# 2021.net
KiCad netlist of a schematic drawn in Altium Designer
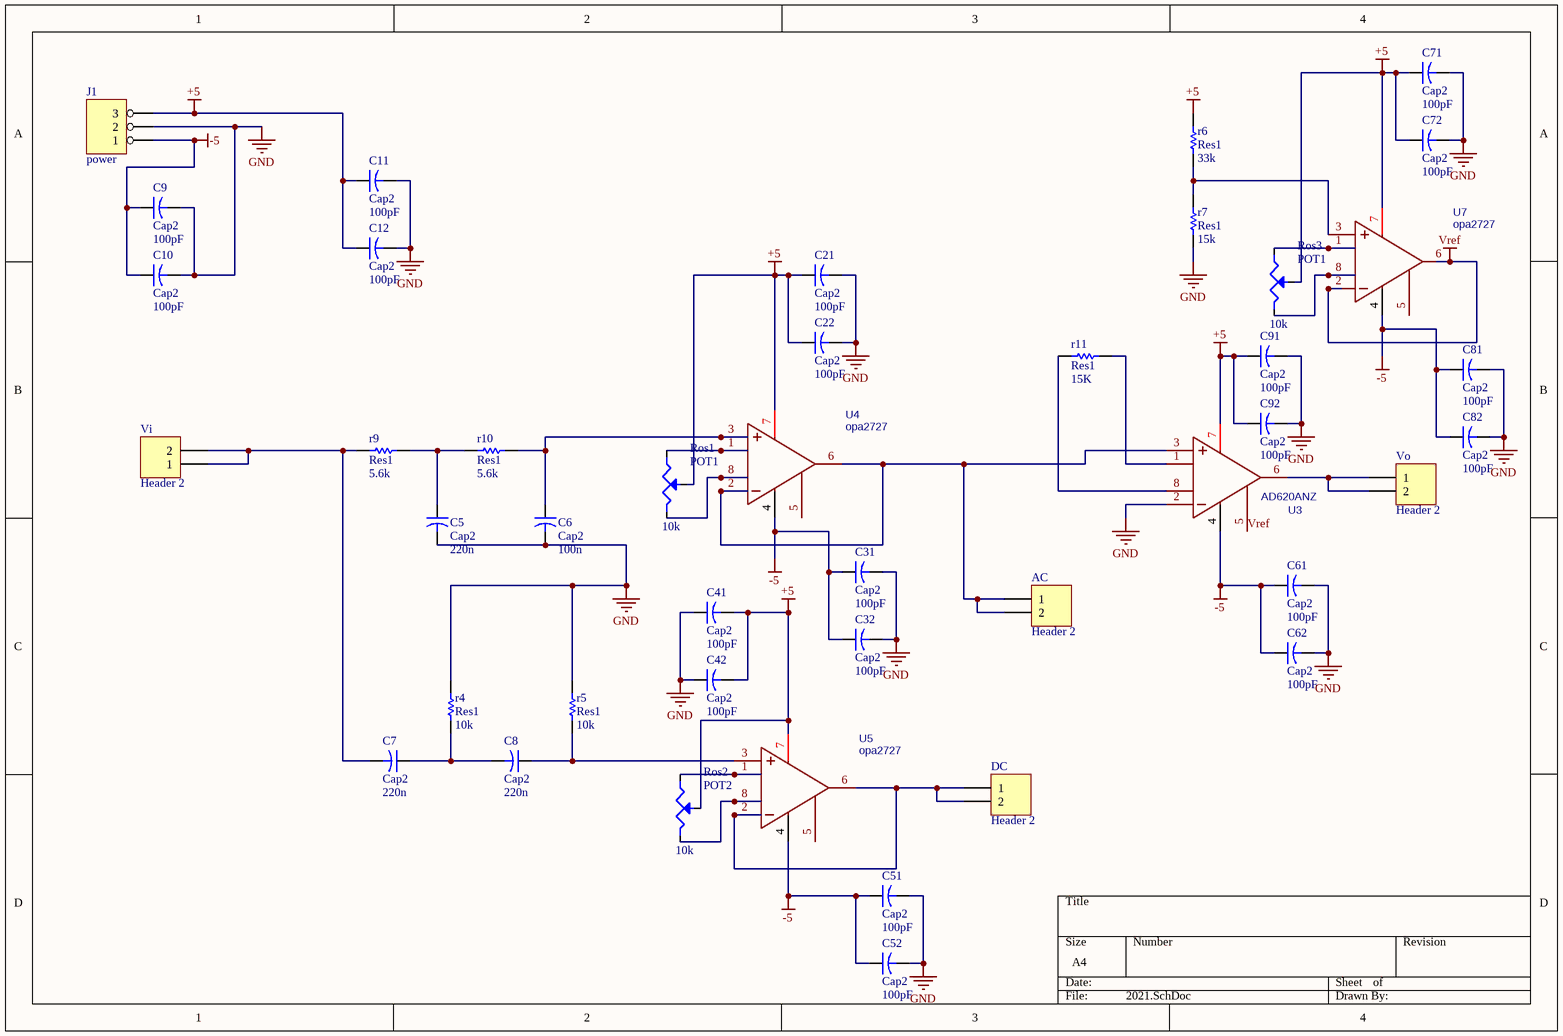
[diagram p0: 2021.SchDoc]

(export (version "E")
  (design (tool "Eeschema 10.0.6"))
  (components
    (comp (ref "AC")
      (value "Header 2")
      (footprint "HDR1X2")
      (description "Header, 2-Pin")
      (fields (field (name "PUBLISHER") "Altium Limited"))
      (libsource (lib "") (part "Header 2_1"))
    )
    (comp (ref "C5")
      (value "Cap2")
      (footprint "RAD0.2")
      (description "Capacitor")
      (fields (field (name "ALTIUM_VALUE") "220n") (field (name "PUBLISHER") "Altium Limited"))
      (libsource (lib "Miscellaneous Devices") (part "Cap2"))
    )
    (comp (ref "C6")
      (value "Cap2")
      (footprint "RAD0.2")
      (description "Capacitor")
      (fields (field (name "ALTIUM_VALUE") "100n") (field (name "PUBLISHER") "Altium Limited"))
      (libsource (lib "Miscellaneous Devices") (part "Cap2"))
    )
    (comp (ref "C7")
      (value "Cap2")
      (footprint "RAD0.2")
      (description "Capacitor")
      (fields (field (name "ALTIUM_VALUE") "220n") (field (name "PUBLISHER") "Altium Limited"))
      (libsource (lib "Miscellaneous Devices") (part "Cap2"))
    )
    (comp (ref "C8")
      (value "Cap2")
      (footprint "RAD0.2")
      (description "Capacitor")
      (fields (field (name "ALTIUM_VALUE") "220n") (field (name "PUBLISHER") "Altium Limited"))
      (libsource (lib "Miscellaneous Devices") (part "Cap2"))
    )
    (comp (ref "C9")
      (value "Cap2")
      (footprint "RAD0.2")
      (description "Capacitor")
      (fields (field (name "ALTIUM_VALUE") "100pF") (field (name "PUBLISHER") "Altium Limited"))
      (libsource (lib "Miscellaneous Devices") (part "Cap2"))
    )
    (comp (ref "C10")
      (value "Cap2")
      (footprint "RAD0.2")
      (description "Capacitor")
      (fields (field (name "ALTIUM_VALUE") "100pF") (field (name "PUBLISHER") "Altium Limited"))
      (libsource (lib "Miscellaneous Devices") (part "Cap2"))
    )
    (comp (ref "C11")
      (value "Cap2")
      (footprint "RAD0.2")
      (description "Capacitor")
      (fields (field (name "ALTIUM_VALUE") "100pF") (field (name "PUBLISHER") "Altium Limited"))
      (libsource (lib "Miscellaneous Devices") (part "Cap2"))
    )
    (comp (ref "C12")
      (value "Cap2")
      (footprint "RAD0.2")
      (description "Capacitor")
      (fields (field (name "ALTIUM_VALUE") "100pF") (field (name "PUBLISHER") "Altium Limited"))
      (libsource (lib "Miscellaneous Devices") (part "Cap2"))
    )
    (comp (ref "C21")
      (value "Cap2")
      (footprint "RAD0.2")
      (description "Capacitor")
      (fields (field (name "ALTIUM_VALUE") "100pF") (field (name "PUBLISHER") "Altium Limited"))
      (libsource (lib "Miscellaneous Devices") (part "Cap2"))
    )
    (comp (ref "C22")
      (value "Cap2")
      (footprint "RAD0.2")
      (description "Capacitor")
      (fields (field (name "ALTIUM_VALUE") "100pF") (field (name "PUBLISHER") "Altium Limited"))
      (libsource (lib "Miscellaneous Devices") (part "Cap2"))
    )
    (comp (ref "C31")
      (value "Cap2")
      (footprint "RAD0.2")
      (description "Capacitor")
      (fields (field (name "ALTIUM_VALUE") "100pF") (field (name "PUBLISHER") "Altium Limited"))
      (libsource (lib "Miscellaneous Devices") (part "Cap2"))
    )
    (comp (ref "C32")
      (value "Cap2")
      (footprint "RAD0.2")
      (description "Capacitor")
      (fields (field (name "ALTIUM_VALUE") "100pF") (field (name "PUBLISHER") "Altium Limited"))
      (libsource (lib "Miscellaneous Devices") (part "Cap2"))
    )
    (comp (ref "C41")
      (value "Cap2")
      (footprint "RAD0.2")
      (description "Capacitor")
      (fields (field (name "ALTIUM_VALUE") "100pF") (field (name "PUBLISHER") "Altium Limited"))
      (libsource (lib "Miscellaneous Devices") (part "Cap2"))
    )
    (comp (ref "C42")
      (value "Cap2")
      (footprint "RAD0.2")
      (description "Capacitor")
      (fields (field (name "ALTIUM_VALUE") "100pF") (field (name "PUBLISHER") "Altium Limited"))
      (libsource (lib "Miscellaneous Devices") (part "Cap2"))
    )
    (comp (ref "C51")
      (value "Cap2")
      (footprint "RAD0.2")
      (description "Capacitor")
      (fields (field (name "ALTIUM_VALUE") "100pF") (field (name "PUBLISHER") "Altium Limited"))
      (libsource (lib "Miscellaneous Devices") (part "Cap2"))
    )
    (comp (ref "C52")
      (value "Cap2")
      (footprint "RAD0.2")
      (description "Capacitor")
      (fields (field (name "ALTIUM_VALUE") "100pF") (field (name "PUBLISHER") "Altium Limited"))
      (libsource (lib "Miscellaneous Devices") (part "Cap2"))
    )
    (comp (ref "C61")
      (value "Cap2")
      (footprint "RAD0.2")
      (description "Capacitor")
      (fields (field (name "ALTIUM_VALUE") "100pF") (field (name "PUBLISHER") "Altium Limited"))
      (libsource (lib "Miscellaneous Devices") (part "Cap2"))
    )
    (comp (ref "C62")
      (value "Cap2")
      (footprint "RAD0.2")
      (description "Capacitor")
      (fields (field (name "ALTIUM_VALUE") "100pF") (field (name "PUBLISHER") "Altium Limited"))
      (libsource (lib "Miscellaneous Devices") (part "Cap2"))
    )
    (comp (ref "C71")
      (value "Cap2")
      (footprint "RAD0.2")
      (description "Capacitor")
      (fields (field (name "ALTIUM_VALUE") "100pF") (field (name "PUBLISHER") "Altium Limited"))
      (libsource (lib "Miscellaneous Devices") (part "Cap2"))
    )
    (comp (ref "C72")
      (value "Cap2")
      (footprint "RAD0.2")
      (description "Capacitor")
      (fields (field (name "ALTIUM_VALUE") "100pF") (field (name "PUBLISHER") "Altium Limited"))
      (libsource (lib "Miscellaneous Devices") (part "Cap2"))
    )
    (comp (ref "C81")
      (value "Cap2")
      (footprint "RAD0.2")
      (description "Capacitor")
      (fields (field (name "ALTIUM_VALUE") "100pF") (field (name "PUBLISHER") "Altium Limited"))
      (libsource (lib "Miscellaneous Devices") (part "Cap2"))
    )
    (comp (ref "C82")
      (value "Cap2")
      (footprint "RAD0.2")
      (description "Capacitor")
      (fields (field (name "ALTIUM_VALUE") "100pF") (field (name "PUBLISHER") "Altium Limited"))
      (libsource (lib "Miscellaneous Devices") (part "Cap2"))
    )
    (comp (ref "C91")
      (value "Cap2")
      (footprint "RAD0.2")
      (description "Capacitor")
      (fields (field (name "ALTIUM_VALUE") "100pF") (field (name "PUBLISHER") "Altium Limited"))
      (libsource (lib "Miscellaneous Devices") (part "Cap2"))
    )
    (comp (ref "C92")
      (value "Cap2")
      (footprint "RAD0.2")
      (description "Capacitor")
      (fields (field (name "ALTIUM_VALUE") "100pF") (field (name "PUBLISHER") "Altium Limited"))
      (libsource (lib "Miscellaneous Devices") (part "Cap2"))
    )
    (comp (ref "DC")
      (value "Header 2")
      (footprint "HDR1X2")
      (description "Header, 2-Pin")
      (fields (field (name "PUBLISHER") "Altium Limited"))
      (libsource (lib "") (part "Header 2_1"))
    )
    (comp (ref "J1")
      (value "power")
      (footprint "SIP3")
      (libsource (lib "Miscellaneous Devices") (part "HEADER 3"))
    )
    (comp (ref "r4")
      (value "Res1")
      (footprint "AXIAL0.4")
      (description "Resistor")
      (fields (field (name "ALTIUM_VALUE") "10k") (field (name "PUBLISHER") "Altium Limited"))
      (libsource (lib "Miscellaneous Devices") (part "Res1"))
    )
    (comp (ref "r5")
      (value "Res1")
      (footprint "AXIAL0.4")
      (description "Resistor")
      (fields (field (name "ALTIUM_VALUE") "10k") (field (name "PUBLISHER") "Altium Limited"))
      (libsource (lib "Miscellaneous Devices") (part "Res1"))
    )
    (comp (ref "r6")
      (value "Res1")
      (footprint "AXIAL-0.4")
      (description "Resistor")
      (fields (field (name "ALTIUM_VALUE") "33k") (field (name "PUBLISHER") "Altium Limited"))
      (libsource (lib "Miscellaneous Devices") (part "Res1"))
    )
    (comp (ref "r7")
      (value "Res1")
      (footprint "AXIAL0.4")
      (description "Resistor")
      (fields (field (name "ALTIUM_VALUE") "15k") (field (name "PUBLISHER") "Altium Limited"))
      (libsource (lib "Miscellaneous Devices") (part "Res1"))
    )
    (comp (ref "r9")
      (value "Res1")
      (footprint "AXIAL0.4")
      (description "Resistor")
      (fields (field (name "ALTIUM_VALUE") "5.6k") (field (name "PUBLISHER") "Altium Limited"))
      (libsource (lib "Miscellaneous Devices") (part "Res1"))
    )
    (comp (ref "r10")
      (value "Res1")
      (footprint "AXIAL0.4")
      (description "Resistor")
      (fields (field (name "ALTIUM_VALUE") "5.6k") (field (name "PUBLISHER") "Altium Limited"))
      (libsource (lib "Miscellaneous Devices") (part "Res1"))
    )
    (comp (ref "r11")
      (value "Res1")
      (footprint "AXIAL0.4")
      (description "Resistor")
      (fields (field (name "ALTIUM_VALUE") "15K") (field (name "PUBLISHER") "Altium Limited"))
      (libsource (lib "Miscellaneous Devices") (part "Res1"))
    )
    (comp (ref "Ros1")
      (value "POT1")
      (footprint "VR5")
      (description "Potentiometer")
      (fields (field (name "ALTIUM_VALUE") "10k"))
      (libsource (lib "Miscellaneous Devices") (part "POT1"))
    )
    (comp (ref "Ros2")
      (value "POT2")
      (footprint "VR5")
      (description "Potentiometer")
      (fields (field (name "ALTIUM_VALUE") "10k"))
      (libsource (lib "Miscellaneous Devices") (part "POT1"))
    )
    (comp (ref "Ros3")
      (value "POT1")
      (footprint "VR5")
      (description "Potentiometer")
      (fields (field (name "ALTIUM_VALUE") "10k"))
      (libsource (lib "Miscellaneous Devices") (part "POT1"))
    )
    (comp (ref "U3")
      (value "AD620ANZ")
      (footprint "DIP8")
      (fields (field (name "BOM_SUPPLIER PART") "C9680"))
      (libsource (lib "AD620ANZ") (part "AD620ANZ"))
    )
    (comp (ref "U4")
      (value "opa2727")
      (footprint "DIP8")
      (fields (field (name "BOM_MANUFACTURER PART") "AD620ANZ") (field (name "BOM_SUPPLIER PART") "C9680"))
      (libsource (lib "AD620ANZ") (part "AD620ANZ"))
    )
    (comp (ref "U5")
      (value "opa2727")
      (footprint "DIP8")
      (fields (field (name "BOM_MANUFACTURER PART") "AD620ANZ") (field (name "BOM_SUPPLIER PART") "C9680"))
      (libsource (lib "AD620ANZ") (part "AD620ANZ"))
    )
    (comp (ref "U7")
      (value "opa2727")
      (footprint "DIP8")
      (fields (field (name "BOM_MANUFACTURER PART") "AD620ANZ") (field (name "BOM_SUPPLIER PART") "C9680"))
      (libsource (lib "AD620ANZ") (part "AD620ANZ"))
    )
    (comp (ref "Vi")
      (value "Header 2")
      (footprint "HDR1X2")
      (description "Header, 2-Pin")
      (fields (field (name "PUBLISHER") "Altium Limited"))
      (libsource (lib "Miscellaneous Connectors") (part "Header 2"))
    )
    (comp (ref "Vo")
      (value "Header 2")
      (footprint "HDR1X2")
      (description "Header, 2-Pin")
      (fields (field (name "PUBLISHER") "Altium Limited"))
      (libsource (lib "") (part "Header 2_1"))
    )
  )
  (nets
    (net (code "1") (name "+5") (class "Default")
      (node (ref "C11") (pin "1") (pinfunction "1_1") (pintype "passive"))
      (node (ref "C12") (pin "1") (pinfunction "1_1") (pintype "passive"))
      (node (ref "C21") (pin "1") (pinfunction "1_1") (pintype "passive"))
      (node (ref "C22") (pin "1") (pinfunction "1_1") (pintype "passive"))
      (node (ref "C41") (pin "2") (pinfunction "2_2") (pintype "passive"))
      (node (ref "C42") (pin "2") (pinfunction "2_2") (pintype "passive"))
      (node (ref "C71") (pin "1") (pinfunction "1_1") (pintype "passive"))
      (node (ref "C72") (pin "1") (pinfunction "1_1") (pintype "passive"))
      (node (ref "C91") (pin "1") (pinfunction "1_1") (pintype "passive"))
      (node (ref "C92") (pin "1") (pinfunction "1_1") (pintype "passive"))
      (node (ref "J1") (pin "3") (pinfunction "3_3") (pintype "passive"))
      (node (ref "Ros1") (pin "3") (pinfunction "W_3") (pintype "passive"))
      (node (ref "Ros2") (pin "3") (pinfunction "W_3") (pintype "passive"))
      (node (ref "Ros3") (pin "3") (pinfunction "W_3") (pintype "passive"))
      (node (ref "U3") (pin "7") (pinfunction "+VS_7") (pintype "passive"))
      (node (ref "U4") (pin "7") (pinfunction "+VS_7") (pintype "passive"))
      (node (ref "U5") (pin "7") (pinfunction "+VS_7") (pintype "passive"))
      (node (ref "U7") (pin "7") (pinfunction "+VS_7") (pintype "passive"))
      (node (ref "r6") (pin "2") (pinfunction "2_2") (pintype "passive"))
    )
    (net (code "2") (name "-5") (class "Default")
      (node (ref "C10") (pin "1") (pinfunction "1_1") (pintype "passive"))
      (node (ref "C31") (pin "1") (pinfunction "1_1") (pintype "passive"))
      (node (ref "C32") (pin "1") (pinfunction "1_1") (pintype "passive"))
      (node (ref "C51") (pin "1") (pinfunction "1_1") (pintype "passive"))
      (node (ref "C52") (pin "1") (pinfunction "1_1") (pintype "passive"))
      (node (ref "C61") (pin "1") (pinfunction "1_1") (pintype "passive"))
      (node (ref "C62") (pin "1") (pinfunction "1_1") (pintype "passive"))
      (node (ref "C81") (pin "1") (pinfunction "1_1") (pintype "passive"))
      (node (ref "C82") (pin "1") (pinfunction "1_1") (pintype "passive"))
      (node (ref "C9") (pin "1") (pinfunction "1_1") (pintype "passive"))
      (node (ref "J1") (pin "1") (pinfunction "1_1") (pintype "passive"))
      (node (ref "U3") (pin "4") (pinfunction "-VS_4") (pintype "passive"))
      (node (ref "U4") (pin "4") (pinfunction "-VS_4") (pintype "passive"))
      (node (ref "U5") (pin "4") (pinfunction "-VS_4") (pintype "passive"))
      (node (ref "U7") (pin "4") (pinfunction "-VS_4") (pintype "passive"))
    )
    (net (code "3") (name "GND") (class "Default")
      (node (ref "C10") (pin "2") (pinfunction "2_2") (pintype "passive"))
      (node (ref "C11") (pin "2") (pinfunction "2_2") (pintype "passive"))
      (node (ref "C12") (pin "2") (pinfunction "2_2") (pintype "passive"))
      (node (ref "C21") (pin "2") (pinfunction "2_2") (pintype "passive"))
      (node (ref "C22") (pin "2") (pinfunction "2_2") (pintype "passive"))
      (node (ref "C31") (pin "2") (pinfunction "2_2") (pintype "passive"))
      (node (ref "C32") (pin "2") (pinfunction "2_2") (pintype "passive"))
      (node (ref "C41") (pin "1") (pinfunction "1_1") (pintype "passive"))
      (node (ref "C42") (pin "1") (pinfunction "1_1") (pintype "passive"))
      (node (ref "C5") (pin "2") (pinfunction "2_2") (pintype "passive"))
      (node (ref "C51") (pin "2") (pinfunction "2_2") (pintype "passive"))
      (node (ref "C52") (pin "2") (pinfunction "2_2") (pintype "passive"))
      (node (ref "C6") (pin "2") (pinfunction "2_2") (pintype "passive"))
      (node (ref "C61") (pin "2") (pinfunction "2_2") (pintype "passive"))
      (node (ref "C62") (pin "2") (pinfunction "2_2") (pintype "passive"))
      (node (ref "C71") (pin "2") (pinfunction "2_2") (pintype "passive"))
      (node (ref "C72") (pin "2") (pinfunction "2_2") (pintype "passive"))
      (node (ref "C81") (pin "2") (pinfunction "2_2") (pintype "passive"))
      (node (ref "C82") (pin "2") (pinfunction "2_2") (pintype "passive"))
      (node (ref "C9") (pin "2") (pinfunction "2_2") (pintype "passive"))
      (node (ref "C91") (pin "2") (pinfunction "2_2") (pintype "passive"))
      (node (ref "C92") (pin "2") (pinfunction "2_2") (pintype "passive"))
      (node (ref "J1") (pin "2") (pinfunction "2_2") (pintype "passive"))
      (node (ref "U3") (pin "2") (pinfunction "-IN_2") (pintype "passive"))
      (node (ref "r4") (pin "2") (pinfunction "2_2") (pintype "passive"))
      (node (ref "r5") (pin "2") (pinfunction "2_2") (pintype "passive"))
      (node (ref "r7") (pin "1") (pinfunction "1_1") (pintype "passive"))
    )
    (net (code "4") (name "Net-(C5-Pad1)") (class "Default")
      (node (ref "C5") (pin "1") (pinfunction "1_1") (pintype "passive"))
      (node (ref "r10") (pin "1") (pinfunction "1_1") (pintype "passive"))
      (node (ref "r9") (pin "2") (pinfunction "2_2") (pintype "passive"))
    )
    (net (code "5") (name "Net-(C7-Pad1)") (class "Default")
      (node (ref "C7") (pin "1") (pinfunction "1_1") (pintype "passive"))
      (node (ref "C8") (pin "2") (pinfunction "2_2") (pintype "passive"))
      (node (ref "r4") (pin "1") (pinfunction "1_1") (pintype "passive"))
    )
    (net (code "6") (name "Net-(C7-Pad2)") (class "Default")
      (node (ref "C7") (pin "2") (pinfunction "2_2") (pintype "passive"))
      (node (ref "Vi") (pin "1") (pinfunction "1_1") (pintype "passive"))
      (node (ref "Vi") (pin "2") (pinfunction "2_2") (pintype "passive"))
      (node (ref "r9") (pin "1") (pinfunction "1_1") (pintype "passive"))
    )
    (net (code "7") (name "Net-(Ros1-Pad1)") (class "Default")
      (node (ref "Ros1") (pin "1") (pinfunction "1_1") (pintype "passive"))
      (node (ref "U4") (pin "1") (pinfunction "RG_1") (pintype "passive"))
    )
    (net (code "8") (name "Net-(Ros1-Pad2)") (class "Default")
      (node (ref "Ros1") (pin "2") (pinfunction "2_2") (pintype "passive"))
      (node (ref "U4") (pin "8") (pinfunction "RG_8") (pintype "passive"))
    )
    (net (code "9") (name "Net-(Ros2-Pad1)") (class "Default")
      (node (ref "Ros2") (pin "1") (pinfunction "1_1") (pintype "passive"))
      (node (ref "U5") (pin "1") (pinfunction "RG_1") (pintype "passive"))
    )
    (net (code "10") (name "Net-(Ros2-Pad2)") (class "Default")
      (node (ref "Ros2") (pin "2") (pinfunction "2_2") (pintype "passive"))
      (node (ref "U5") (pin "8") (pinfunction "RG_8") (pintype "passive"))
    )
    (net (code "11") (name "Net-(Ros3-Pad1)") (class "Default")
      (node (ref "Ros3") (pin "1") (pinfunction "1_1") (pintype "passive"))
      (node (ref "U7") (pin "1") (pinfunction "RG_1") (pintype "passive"))
    )
    (net (code "12") (name "Net-(Ros3-Pad2)") (class "Default")
      (node (ref "Ros3") (pin "2") (pinfunction "2_2") (pintype "passive"))
      (node (ref "U7") (pin "8") (pinfunction "RG_8") (pintype "passive"))
    )
    (net (code "13") (name "Net-(U3-+IN)") (class "Default")
      (node (ref "AC") (pin "1") (pinfunction "1_1") (pintype "passive"))
      (node (ref "AC") (pin "2") (pinfunction "2_2") (pintype "passive"))
      (node (ref "U3") (pin "3") (pinfunction "+IN_3") (pintype "passive"))
      (node (ref "U4") (pin "2") (pinfunction "-IN_2") (pintype "passive"))
      (node (ref "U4") (pin "6") (pinfunction "OUTPUT_6") (pintype "passive"))
    )
    (net (code "14") (name "Net-(U3-OUTPUT)") (class "Default")
      (node (ref "U3") (pin "6") (pinfunction "OUTPUT_6") (pintype "passive"))
      (node (ref "Vo") (pin "1") (pinfunction "1_1") (pintype "passive"))
      (node (ref "Vo") (pin "2") (pinfunction "2_2") (pintype "passive"))
    )
    (net (code "15") (name "Net-(U3-RG-Pad1)") (class "Default")
      (node (ref "U3") (pin "1") (pinfunction "RG_1") (pintype "passive"))
      (node (ref "r11") (pin "2") (pinfunction "2_2") (pintype "passive"))
    )
    (net (code "16") (name "Net-(U3-RG-Pad8)") (class "Default")
      (node (ref "U3") (pin "8") (pinfunction "RG_8") (pintype "passive"))
      (node (ref "r11") (pin "1") (pinfunction "1_1") (pintype "passive"))
    )
    (net (code "17") (name "Net-(U4-+IN)") (class "Default")
      (node (ref "C6") (pin "1") (pinfunction "1_1") (pintype "passive"))
      (node (ref "U4") (pin "3") (pinfunction "+IN_3") (pintype "passive"))
      (node (ref "r10") (pin "2") (pinfunction "2_2") (pintype "passive"))
    )
    (net (code "18") (name "Net-(U5-+IN)") (class "Default")
      (node (ref "C8") (pin "1") (pinfunction "1_1") (pintype "passive"))
      (node (ref "U5") (pin "3") (pinfunction "+IN_3") (pintype "passive"))
      (node (ref "r5") (pin "1") (pinfunction "1_1") (pintype "passive"))
    )
    (net (code "19") (name "Net-(U5--IN)") (class "Default")
      (node (ref "DC") (pin "1") (pinfunction "1_1") (pintype "passive"))
      (node (ref "DC") (pin "2") (pinfunction "2_2") (pintype "passive"))
      (node (ref "U5") (pin "2") (pinfunction "-IN_2") (pintype "passive"))
      (node (ref "U5") (pin "6") (pinfunction "OUTPUT_6") (pintype "passive"))
    )
    (net (code "20") (name "Net-(U7-+IN)") (class "Default")
      (node (ref "U7") (pin "3") (pinfunction "+IN_3") (pintype "passive"))
      (node (ref "r6") (pin "1") (pinfunction "1_1") (pintype "passive"))
      (node (ref "r7") (pin "2") (pinfunction "2_2") (pintype "passive"))
    )
    (net (code "21") (name "Vref") (class "Default")
      (node (ref "U3") (pin "5") (pinfunction "REF_5") (pintype "passive"))
      (node (ref "U7") (pin "2") (pinfunction "-IN_2") (pintype "passive"))
      (node (ref "U7") (pin "6") (pinfunction "OUTPUT_6") (pintype "passive"))
    )
    (net (code "22") (name "unconnected-(U4-REF-Pad5)") (class "Default")
      (node (ref "U4") (pin "5") (pinfunction "REF_5") (pintype "passive"))
    )
    (net (code "23") (name "unconnected-(U5-REF-Pad5)") (class "Default")
      (node (ref "U5") (pin "5") (pinfunction "REF_5") (pintype "passive"))
    )
    (net (code "24") (name "unconnected-(U7-REF-Pad5)") (class "Default")
      (node (ref "U7") (pin "5") (pinfunction "REF_5") (pintype "passive"))
    )
  )
)
